# K10P100_V1_0.net
KiCad netlist of a schematic drawn in Altium Designer
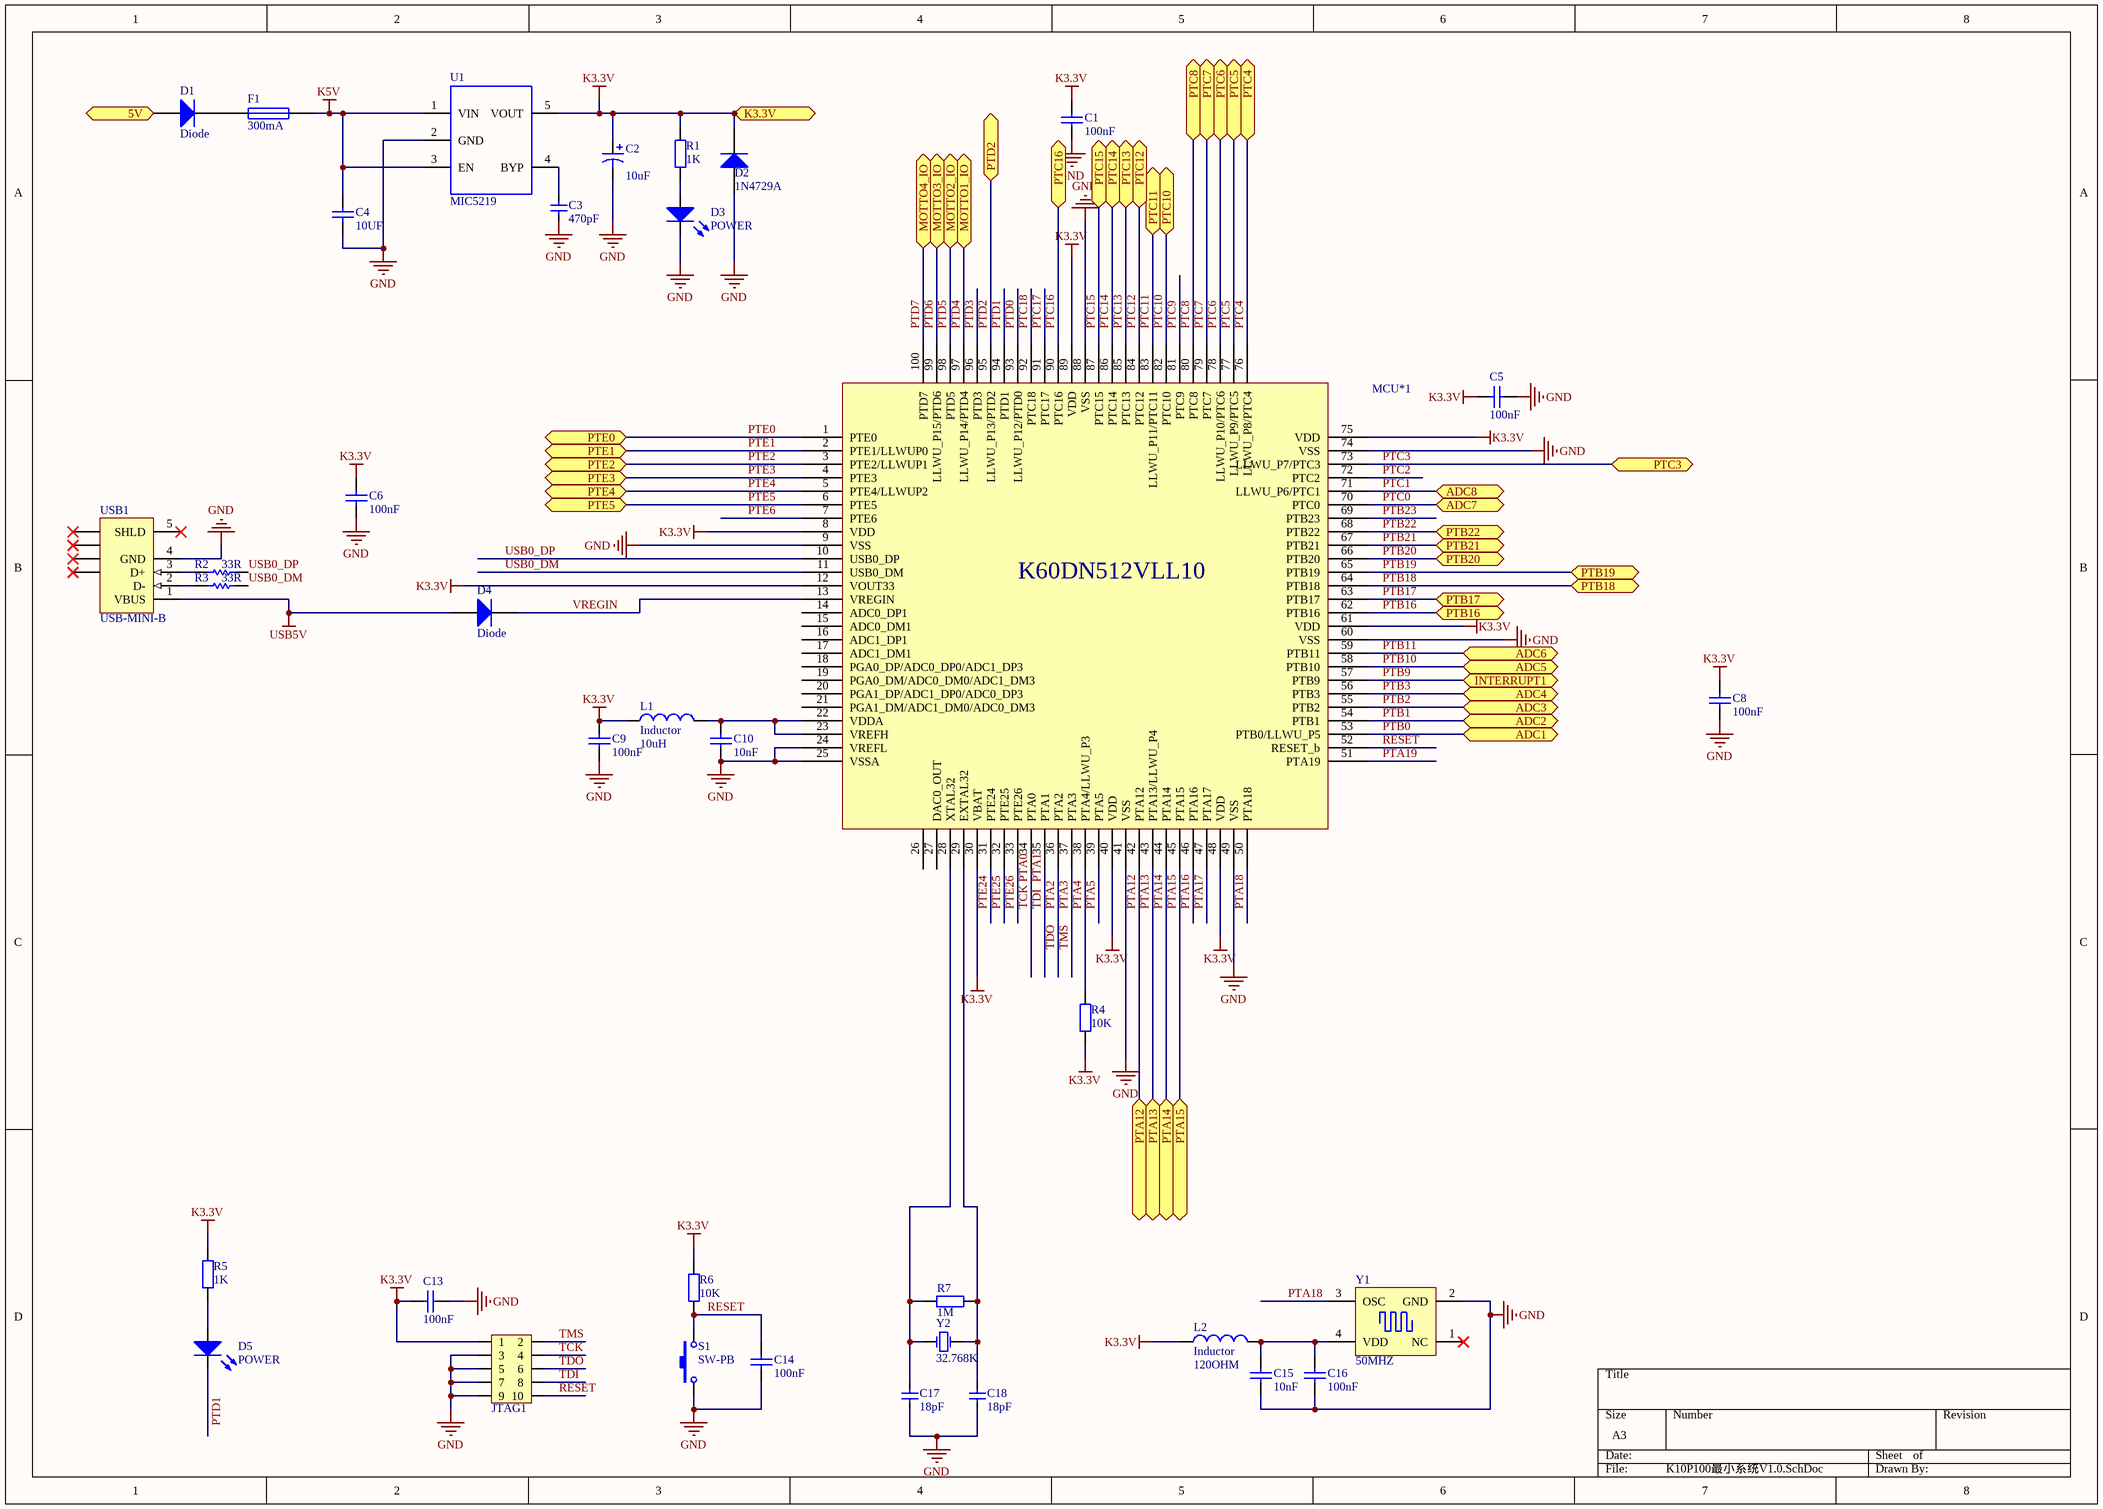
[diagram p0: K10P100最小系统V1.0.SchDoc]

(export (version "E")
  (design (tool "Eeschema 10.0.6"))
  (components
    (comp (ref "C1")
      (value "100nF")
      (footprint "C2012")
      (description "Capacitor")
      (libsource (lib "K60-V4.0") (part "Cap"))
    )
    (comp (ref "C2")
      (value "10uF")
      (footprint "C2012")
      (description "Polarized Capacitor (Radial)")
      (fields (field (name "Comment") "Cap Pol1") (field (name "PUBLISHER") "Altium Limited"))
      (libsource (lib "Miscellaneous Devices") (part "Cap Pol1"))
    )
    (comp (ref "C3")
      (value "470pF")
      (footprint "C2012")
      (description "CAP")
      (libsource (lib "K60-V4.0") (part "陶瓷电容"))
    )
    (comp (ref "C4")
      (value "10UF")
      (footprint "C2012")
      (description "Capacitor")
      (libsource (lib "K60-V4.0") (part "Cap"))
    )
    (comp (ref "C5")
      (value "100nF")
      (footprint "C2012")
      (description "Capacitor")
      (libsource (lib "K60-V4.0") (part "Cap"))
    )
    (comp (ref "C6")
      (value "100nF")
      (footprint "C2012")
      (description "Capacitor")
      (libsource (lib "K60-V4.0") (part "Cap"))
    )
    (comp (ref "C8")
      (value "100nF")
      (footprint "C2012")
      (description "Capacitor")
      (libsource (lib "K60-V4.0") (part "Cap"))
    )
    (comp (ref "C9")
      (value "100nF")
      (footprint "C2012")
      (description "Capacitor")
      (libsource (lib "K60-V4.0") (part "Cap"))
    )
    (comp (ref "C10")
      (value "10nF")
      (footprint "C2012")
      (description "Capacitor")
      (libsource (lib "K60-V4.0") (part "Cap"))
    )
    (comp (ref "C13")
      (value "100nF")
      (footprint "C2012")
      (description "Capacitor")
      (libsource (lib "K60-V4.0") (part "Cap"))
    )
    (comp (ref "C14")
      (value "100nF")
      (footprint "C2012")
      (description "Capacitor")
      (libsource (lib "K60-V4.0") (part "Cap"))
    )
    (comp (ref "C15")
      (value "10nF")
      (footprint "C2012")
      (description "Capacitor")
      (libsource (lib "K60-V4.0") (part "Cap"))
    )
    (comp (ref "C16")
      (value "100nF")
      (footprint "C2012")
      (description "Capacitor")
      (libsource (lib "K60-V4.0") (part "Cap"))
    )
    (comp (ref "C17")
      (value "18pF")
      (footprint "C2012")
      (description "CAP")
      (libsource (lib "K60-V4.0") (part "陶瓷电容"))
    )
    (comp (ref "C18")
      (value "18pF")
      (footprint "C2012")
      (description "CAP")
      (libsource (lib "K60-V4.0") (part "陶瓷电容"))
    )
    (comp (ref "D1")
      (value "Diode")
      (footprint "1206(2)")
      (description "Default Diode")
      (fields (field (name "PUBLISHER") "Altium Limited"))
      (libsource (lib "Miscellaneous Devices") (part "Diode"))
    )
    (comp (ref "D2")
      (value "1N4729A")
      (footprint "C2012")
      (description "High Conductance Fast Diode")
      (fields (field (name "PUBLISHER") "Altium Limited"))
      (libsource (lib "K60-V4.0") (part "Diode 1N4148"))
    )
    (comp (ref "D3")
      (value "POWER")
      (footprint "C2012")
      (description "Typical INFRARED GaAs LED")
      (libsource (lib "K60-V4.0") (part "LED"))
    )
    (comp (ref "D4")
      (value "Diode")
      (footprint "1206(2)")
      (description "Default Diode")
      (fields (field (name "PUBLISHER") "Altium Limited"))
      (libsource (lib "Miscellaneous Devices") (part "Diode"))
    )
    (comp (ref "D5")
      (value "POWER")
      (footprint "C2012")
      (description "Typical INFRARED GaAs LED")
      (libsource (lib "K60-V4.0") (part "LED"))
    )
    (comp (ref "F1")
      (value "300mA")
      (footprint "R2012")
      (description "Fuse")
      (fields (field (name "PUBLISHER") "Altium Limited"))
      (libsource (lib "K60-V4.0") (part "Fuse 1"))
    )
    (comp (ref "JTAG1")
      (value "Header 5X2")
      (footprint "IDC5X2")
      (description "Header, 5-Pin, Dual row")
      (libsource (lib "K60-V4.0") (part "Header 5X2"))
    )
    (comp (ref "L1")
      (value "Inductor")
      (footprint "C2012")
      (fields (field (name "ALTIUM_VALUE") "10uH") (field (name "PUBLISHER") "Altium Limited"))
      (libsource (lib "Miscellaneous Devices") (part "Inductor"))
    )
    (comp (ref "L2")
      (value "Inductor")
      (footprint "C2012")
      (fields (field (name "ALTIUM_VALUE") "120OHM") (field (name "PUBLISHER") "Altium Limited"))
      (libsource (lib "Miscellaneous Devices") (part "Inductor"))
    )
    (comp (ref "MCU*1") (value "k60P100") (footprint "LQFP100") (libsource (lib "原理图") (part "k60P100")))
    (comp (ref "R1")
      (value "1K")
      (footprint "R2012")
      (description "Resistor of led")
      (libsource (lib "K60-V4.0") (part "Res"))
    )
    (comp (ref "R2")
      (value "33R")
      (footprint "R2012")
      (description "贴片电阻")
      (fields (field (name "PUBLISHER") "Altium Limited"))
      (libsource (lib "Sparks") (part "Res"))
    )
    (comp (ref "R3")
      (value "33R")
      (footprint "R2012")
      (description "贴片电阻")
      (fields (field (name "PUBLISHER") "Altium Limited"))
      (libsource (lib "Sparks") (part "Res"))
    )
    (comp (ref "R4")
      (value "10K")
      (footprint "R2012")
      (description "Resistor of led")
      (libsource (lib "K60-V4.0") (part "Res"))
    )
    (comp (ref "R5")
      (value "1K")
      (footprint "R2012")
      (description "Resistor of led")
      (libsource (lib "K60-V4.0") (part "Res"))
    )
    (comp (ref "R6")
      (value "10K")
      (footprint "R2012")
      (description "Resistor")
      (libsource (lib "K60-V4.0") (part "Res"))
    )
    (comp (ref "R7")
      (value "1M")
      (footprint "R2012")
      (description "Resistor")
      (libsource (lib "") (part "Res_1"))
    )
    (comp (ref "S1")
      (value "SW-PB")
      (footprint "sw 3*4 *2")
      (description "Switch")
      (libsource (lib "K60-V4.0") (part "SW-PB"))
    )
    (comp (ref "U1")
      (value "MIC5219")
      (footprint "SOT-23-5")
      (description "LDO")
      (libsource (lib "K60-V4.0") (part "MIC5219"))
    )
    (comp (ref "USB1")
      (value "USB-MINI-B")
      (footprint "USB-MINI-B")
      (description "USB 2.0, Right Angle, SMT, A Type, Receptacle, 5 Position, Black")
      (fields (field (name "PUBLISHER") "Altium Limited"))
      (libsource (lib "Sparks") (part "USB-MINI-B"))
    )
    (comp (ref "Y1") (value "50MHZ") (footprint "XTAL7_3225") (libsource (lib "K60-V4.0") (part "XTAL1")))
    (comp (ref "Y2")
      (value "32.768K")
      (footprint "CT3215")
      (description "Crystal Oscillator")
      (libsource (lib "K60-V4.0") (part "XTAL"))
    )
  )
  (nets
    (net (code "1") (name "/5V") (class "Default")
      (node (ref "D1") (pin "1") (pinfunction "A_1") (pintype "passive"))
    )
    (net (code "2") (name "/PTA0") (class "Default")
      (node (ref "JTAG1") (pin "4") (pinfunction "4_4") (pintype "passive"))
      (node (ref "MCU*1") (pin "34") (pinfunction "PTA0_34") (pintype "passive"))
    )
    (net (code "3") (name "/PTA1") (class "Default")
      (node (ref "JTAG1") (pin "8") (pinfunction "8_8") (pintype "passive"))
      (node (ref "MCU*1") (pin "35") (pinfunction "PTA1_35") (pintype "passive"))
    )
    (net (code "4") (name "/PTA2") (class "Default")
      (node (ref "JTAG1") (pin "6") (pinfunction "6_6") (pintype "passive"))
      (node (ref "MCU*1") (pin "36") (pinfunction "PTA2_36") (pintype "passive"))
    )
    (net (code "5") (name "/PTA3") (class "Default")
      (node (ref "JTAG1") (pin "2") (pinfunction "2_2") (pintype "passive"))
      (node (ref "MCU*1") (pin "37") (pinfunction "PTA3_37") (pintype "passive"))
    )
    (net (code "6") (name "/PTA4") (class "Default")
      (node (ref "MCU*1") (pin "38") (pinfunction "PTA4/LLWU_P3_38") (pintype "passive"))
      (node (ref "R4") (pin "2") (pinfunction "2_2") (pintype "passive"))
    )
    (net (code "7") (name "/PTA5") (class "Default")
      (node (ref "MCU*1") (pin "39") (pinfunction "PTA5_39") (pintype "passive"))
    )
    (net (code "8") (name "/PTA12") (class "Default")
      (node (ref "MCU*1") (pin "42") (pinfunction "PTA12_42") (pintype "passive"))
    )
    (net (code "9") (name "/PTA13") (class "Default")
      (node (ref "MCU*1") (pin "43") (pinfunction "PTA13/LLWU_P4_43") (pintype "passive"))
    )
    (net (code "10") (name "/PTA14") (class "Default")
      (node (ref "MCU*1") (pin "44") (pinfunction "PTA14_44") (pintype "passive"))
    )
    (net (code "11") (name "/PTA15") (class "Default")
      (node (ref "MCU*1") (pin "45") (pinfunction "PTA15_45") (pintype "passive"))
    )
    (net (code "12") (name "/PTA16") (class "Default")
      (node (ref "MCU*1") (pin "46") (pinfunction "PTA16_46") (pintype "passive"))
    )
    (net (code "13") (name "/PTA17") (class "Default")
      (node (ref "MCU*1") (pin "47") (pinfunction "PTA17_47") (pintype "passive"))
    )
    (net (code "14") (name "/PTA18") (class "Default")
      (node (ref "MCU*1") (pin "50") (pinfunction "PTA18_50") (pintype "passive"))
      (node (ref "Y1") (pin "3") (pinfunction "OSC_3") (pintype "passive"))
    )
    (net (code "15") (name "/PTA19") (class "Default")
      (node (ref "MCU*1") (pin "51") (pinfunction "PTA19_51") (pintype "passive"))
    )
    (net (code "16") (name "/PTB0") (class "Default")
      (node (ref "MCU*1") (pin "53") (pinfunction "PTB0/LLWU_P5_53") (pintype "passive"))
    )
    (net (code "17") (name "/PTB1") (class "Default")
      (node (ref "MCU*1") (pin "54") (pinfunction "PTB1_54") (pintype "passive"))
    )
    (net (code "18") (name "/PTB2") (class "Default")
      (node (ref "MCU*1") (pin "55") (pinfunction "PTB2_55") (pintype "passive"))
    )
    (net (code "19") (name "/PTB3") (class "Default")
      (node (ref "MCU*1") (pin "56") (pinfunction "PTB3_56") (pintype "passive"))
    )
    (net (code "20") (name "/PTB9") (class "Default")
      (node (ref "MCU*1") (pin "57") (pinfunction "PTB9_57") (pintype "passive"))
    )
    (net (code "21") (name "/PTB10") (class "Default")
      (node (ref "MCU*1") (pin "58") (pinfunction "PTB10_58") (pintype "passive"))
    )
    (net (code "22") (name "/PTB11") (class "Default")
      (node (ref "MCU*1") (pin "59") (pinfunction "PTB11_59") (pintype "passive"))
    )
    (net (code "23") (name "/PTB16") (class "Default")
      (node (ref "MCU*1") (pin "62") (pinfunction "PTB16_62") (pintype "passive"))
    )
    (net (code "24") (name "/PTB17") (class "Default")
      (node (ref "MCU*1") (pin "63") (pinfunction "PTB17_63") (pintype "passive"))
    )
    (net (code "25") (name "/PTB18") (class "Default")
      (node (ref "MCU*1") (pin "64") (pinfunction "PTB18_64") (pintype "passive"))
    )
    (net (code "26") (name "/PTB19") (class "Default")
      (node (ref "MCU*1") (pin "65") (pinfunction "PTB19_65") (pintype "passive"))
    )
    (net (code "27") (name "/PTB20") (class "Default")
      (node (ref "MCU*1") (pin "66") (pinfunction "PTB20_66") (pintype "passive"))
    )
    (net (code "28") (name "/PTB21") (class "Default")
      (node (ref "MCU*1") (pin "67") (pinfunction "PTB21_67") (pintype "passive"))
    )
    (net (code "29") (name "/PTB22") (class "Default")
      (node (ref "MCU*1") (pin "68") (pinfunction "PTB22_68") (pintype "passive"))
    )
    (net (code "30") (name "/PTB23") (class "Default")
      (node (ref "MCU*1") (pin "69") (pinfunction "PTB23_69") (pintype "passive"))
    )
    (net (code "31") (name "/PTC0") (class "Default")
      (node (ref "MCU*1") (pin "70") (pinfunction "PTC0_70") (pintype "passive"))
    )
    (net (code "32") (name "/PTC1") (class "Default")
      (node (ref "MCU*1") (pin "71") (pinfunction "LLWU_P6/PTC1_71") (pintype "passive"))
    )
    (net (code "33") (name "/PTC2") (class "Default")
      (node (ref "MCU*1") (pin "72") (pinfunction "PTC2_72") (pintype "passive"))
    )
    (net (code "34") (name "/PTC3") (class "Default")
      (node (ref "MCU*1") (pin "73") (pinfunction "LLWU_P7/PTC3_73") (pintype "passive"))
    )
    (net (code "35") (name "/PTC4") (class "Default")
      (node (ref "MCU*1") (pin "76") (pinfunction "LLWU_P8/PTC4_76") (pintype "passive"))
    )
    (net (code "36") (name "/PTC5") (class "Default")
      (node (ref "MCU*1") (pin "77") (pinfunction "LLWU_P9/PTC5_77") (pintype "passive"))
    )
    (net (code "37") (name "/PTC6") (class "Default")
      (node (ref "MCU*1") (pin "78") (pinfunction "LLWU_P10/PTC6_78") (pintype "passive"))
    )
    (net (code "38") (name "/PTC7") (class "Default")
      (node (ref "MCU*1") (pin "79") (pinfunction "PTC7_79") (pintype "passive"))
    )
    (net (code "39") (name "/PTC8") (class "Default")
      (node (ref "MCU*1") (pin "80") (pinfunction "PTC8_80") (pintype "passive"))
    )
    (net (code "40") (name "/PTC9") (class "Default")
      (node (ref "MCU*1") (pin "81") (pinfunction "PTC9_81") (pintype "passive"))
    )
    (net (code "41") (name "/PTC10") (class "Default")
      (node (ref "MCU*1") (pin "82") (pinfunction "PTC10_82") (pintype "passive"))
    )
    (net (code "42") (name "/PTC11") (class "Default")
      (node (ref "MCU*1") (pin "83") (pinfunction "LLWU_P11/PTC11_83") (pintype "passive"))
    )
    (net (code "43") (name "/PTC12") (class "Default")
      (node (ref "MCU*1") (pin "84") (pinfunction "PTC12_84") (pintype "passive"))
    )
    (net (code "44") (name "/PTC13") (class "Default")
      (node (ref "MCU*1") (pin "85") (pinfunction "PTC13_85") (pintype "passive"))
    )
    (net (code "45") (name "/PTC14") (class "Default")
      (node (ref "MCU*1") (pin "86") (pinfunction "PTC14_86") (pintype "passive"))
    )
    (net (code "46") (name "/PTC15") (class "Default")
      (node (ref "MCU*1") (pin "87") (pinfunction "PTC15_87") (pintype "passive"))
    )
    (net (code "47") (name "/PTC16") (class "Default")
      (node (ref "MCU*1") (pin "90") (pinfunction "PTC16_90") (pintype "passive"))
    )
    (net (code "48") (name "/PTC17") (class "Default")
      (node (ref "MCU*1") (pin "91") (pinfunction "PTC17_91") (pintype "passive"))
    )
    (net (code "49") (name "/PTC18") (class "Default")
      (node (ref "MCU*1") (pin "92") (pinfunction "PTC18_92") (pintype "passive"))
    )
    (net (code "50") (name "/PTD0") (class "Default")
      (node (ref "MCU*1") (pin "93") (pinfunction "LLWU_P12/PTD0_93") (pintype "passive"))
    )
    (net (code "51") (name "/PTD1") (class "Default")
      (node (ref "D5") (pin "2") (pinfunction "2_2") (pintype "passive"))
      (node (ref "MCU*1") (pin "94") (pinfunction "PTD1_94") (pintype "passive"))
    )
    (net (code "52") (name "/PTD2") (class "Default")
      (node (ref "MCU*1") (pin "95") (pinfunction "LLWU_P13/PTD2_95") (pintype "passive"))
    )
    (net (code "53") (name "/PTD3") (class "Default")
      (node (ref "MCU*1") (pin "96") (pinfunction "PTD3_96") (pintype "passive"))
    )
    (net (code "54") (name "/PTD4") (class "Default")
      (node (ref "MCU*1") (pin "97") (pinfunction "LLWU_P14/PTD4_97") (pintype "passive"))
    )
    (net (code "55") (name "/PTD5") (class "Default")
      (node (ref "MCU*1") (pin "98") (pinfunction "PTD5_98") (pintype "passive"))
    )
    (net (code "56") (name "/PTD6") (class "Default")
      (node (ref "MCU*1") (pin "99") (pinfunction "LLWU_P15/PTD6_99") (pintype "passive"))
    )
    (net (code "57") (name "/PTD7") (class "Default")
      (node (ref "MCU*1") (pin "100") (pinfunction "PTD7_100") (pintype "passive"))
    )
    (net (code "58") (name "/PTE0") (class "Default")
      (node (ref "MCU*1") (pin "1") (pinfunction "PTE0_1") (pintype "passive"))
    )
    (net (code "59") (name "/PTE1") (class "Default")
      (node (ref "MCU*1") (pin "2") (pinfunction "PTE1/LLWUP0_2") (pintype "passive"))
    )
    (net (code "60") (name "/PTE2") (class "Default")
      (node (ref "MCU*1") (pin "3") (pinfunction "PTE2/LLWUP1_3") (pintype "passive"))
    )
    (net (code "61") (name "/PTE3") (class "Default")
      (node (ref "MCU*1") (pin "4") (pinfunction "PTE3_4") (pintype "passive"))
    )
    (net (code "62") (name "/PTE4") (class "Default")
      (node (ref "MCU*1") (pin "5") (pinfunction "PTE4/LLWUP2_5") (pintype "passive"))
    )
    (net (code "63") (name "/PTE5") (class "Default")
      (node (ref "MCU*1") (pin "6") (pinfunction "PTE5_6") (pintype "passive"))
    )
    (net (code "64") (name "/PTE6") (class "Default")
      (node (ref "MCU*1") (pin "7") (pinfunction "PTE6_7") (pintype "passive"))
    )
    (net (code "65") (name "/PTE24") (class "Default")
      (node (ref "MCU*1") (pin "31") (pinfunction "PTE24_31") (pintype "passive"))
    )
    (net (code "66") (name "/PTE25") (class "Default")
      (node (ref "MCU*1") (pin "32") (pinfunction "PTE25_32") (pintype "passive"))
    )
    (net (code "67") (name "/PTE26") (class "Default")
      (node (ref "MCU*1") (pin "33") (pinfunction "PTE26_33") (pintype "passive"))
    )
    (net (code "68") (name "/RESET") (class "Default")
      (node (ref "C14") (pin "2") (pinfunction "2_2") (pintype "passive"))
      (node (ref "JTAG1") (pin "10") (pinfunction "10_10") (pintype "passive"))
      (node (ref "MCU*1") (pin "52") (pinfunction "RESET_b_52") (pintype "passive"))
      (node (ref "R6") (pin "1") (pinfunction "1_1") (pintype "passive"))
      (node (ref "S1") (pin "2") (pinfunction "2_2") (pintype "passive"))
    )
    (net (code "69") (name "/USB0_DM") (class "Default")
      (node (ref "MCU*1") (pin "11") (pinfunction "USB0_DM_11") (pintype "passive"))
      (node (ref "R3") (pin "2") (pinfunction "2_2") (pintype "passive"))
    )
    (net (code "70") (name "/USB0_DP") (class "Default")
      (node (ref "MCU*1") (pin "10") (pinfunction "USB0_DP_10") (pintype "passive"))
      (node (ref "R2") (pin "2") (pinfunction "2_2") (pintype "passive"))
    )
    (net (code "71") (name "/VREGIN") (class "Default")
      (node (ref "D4") (pin "2") (pinfunction "K_2") (pintype "passive"))
      (node (ref "MCU*1") (pin "13") (pinfunction "VREGIN_13") (pintype "passive"))
    )
    (net (code "72") (name "GND") (class "Default")
      (node (ref "C1") (pin "1") (pinfunction "1_1") (pintype "passive"))
      (node (ref "C10") (pin "1") (pinfunction "1_1") (pintype "passive"))
      (node (ref "C13") (pin "2") (pinfunction "2_2") (pintype "passive"))
      (node (ref "C14") (pin "1") (pinfunction "1_1") (pintype "passive"))
      (node (ref "C15") (pin "1") (pinfunction "1_1") (pintype "passive"))
      (node (ref "C16") (pin "1") (pinfunction "1_1") (pintype "passive"))
      (node (ref "C17") (pin "1") (pinfunction "1_1") (pintype "passive"))
      (node (ref "C18") (pin "1") (pinfunction "1_1") (pintype "passive"))
      (node (ref "C2") (pin "2") (pinfunction "2_2") (pintype "passive"))
      (node (ref "C3") (pin "1") (pinfunction "1_1") (pintype "passive"))
      (node (ref "C4") (pin "1") (pinfunction "1_1") (pintype "passive"))
      (node (ref "C5") (pin "1") (pinfunction "1_1") (pintype "passive"))
      (node (ref "C6") (pin "1") (pinfunction "1_1") (pintype "passive"))
      (node (ref "C8") (pin "1") (pinfunction "1_1") (pintype "passive"))
      (node (ref "C9") (pin "1") (pinfunction "1_1") (pintype "passive"))
      (node (ref "D2") (pin "1") (pinfunction "A_1") (pintype "passive"))
      (node (ref "D3") (pin "2") (pinfunction "2_2") (pintype "passive"))
      (node (ref "JTAG1") (pin "3") (pinfunction "3_3") (pintype "passive"))
      (node (ref "JTAG1") (pin "5") (pinfunction "5_5") (pintype "passive"))
      (node (ref "JTAG1") (pin "7") (pinfunction "7_7") (pintype "passive"))
      (node (ref "JTAG1") (pin "9") (pinfunction "9_9") (pintype "passive"))
      (node (ref "MCU*1") (pin "24") (pinfunction "VREFL_24") (pintype "passive"))
      (node (ref "MCU*1") (pin "25") (pinfunction "VSSA_25") (pintype "passive"))
      (node (ref "MCU*1") (pin "41") (pinfunction "VSS_41") (pintype "passive"))
      (node (ref "MCU*1") (pin "49") (pinfunction "VSS_49") (pintype "passive"))
      (node (ref "MCU*1") (pin "60") (pinfunction "VSS_60") (pintype "passive"))
      (node (ref "MCU*1") (pin "74") (pinfunction "VSS_74") (pintype "passive"))
      (node (ref "MCU*1") (pin "88") (pinfunction "VSS_88") (pintype "passive"))
      (node (ref "MCU*1") (pin "9") (pinfunction "VSS_9") (pintype "passive"))
      (node (ref "S1") (pin "1") (pinfunction "1_1") (pintype "passive"))
      (node (ref "U1") (pin "2") (pinfunction "GND_2") (pintype "passive"))
      (node (ref "USB1") (pin "4") (pinfunction "GND_4") (pintype "power_in"))
      (node (ref "Y1") (pin "2") (pinfunction "GND_2") (pintype "passive"))
    )
    (net (code "73") (name "K3.3V") (class "Default")
      (node (ref "C1") (pin "2") (pinfunction "2_2") (pintype "passive"))
      (node (ref "C13") (pin "1") (pinfunction "1_1") (pintype "passive"))
      (node (ref "C2") (pin "1") (pinfunction "1_1") (pintype "passive"))
      (node (ref "C5") (pin "2") (pinfunction "2_2") (pintype "passive"))
      (node (ref "C6") (pin "2") (pinfunction "2_2") (pintype "passive"))
      (node (ref "C8") (pin "2") (pinfunction "2_2") (pintype "passive"))
      (node (ref "C9") (pin "2") (pinfunction "2_2") (pintype "passive"))
      (node (ref "D2") (pin "2") (pinfunction "K_2") (pintype "passive"))
      (node (ref "JTAG1") (pin "1") (pinfunction "1_1") (pintype "passive"))
      (node (ref "L1") (pin "1") (pinfunction "1_1") (pintype "passive"))
      (node (ref "L2") (pin "1") (pinfunction "1_1") (pintype "passive"))
      (node (ref "MCU*1") (pin "12") (pinfunction "VOUT33_12") (pintype "passive"))
      (node (ref "MCU*1") (pin "30") (pinfunction "VBAT_30") (pintype "passive"))
      (node (ref "MCU*1") (pin "40") (pinfunction "VDD_40") (pintype "passive"))
      (node (ref "MCU*1") (pin "48") (pinfunction "VDD_48") (pintype "passive"))
      (node (ref "MCU*1") (pin "61") (pinfunction "VDD_61") (pintype "passive"))
      (node (ref "MCU*1") (pin "75") (pinfunction "VDD_75") (pintype "passive"))
      (node (ref "MCU*1") (pin "8") (pinfunction "VDD_8") (pintype "passive"))
      (node (ref "MCU*1") (pin "89") (pinfunction "VDD_89") (pintype "passive"))
      (node (ref "R1") (pin "2") (pinfunction "2_2") (pintype "passive"))
      (node (ref "R4") (pin "1") (pinfunction "1_1") (pintype "passive"))
      (node (ref "R5") (pin "2") (pinfunction "2_2") (pintype "passive"))
      (node (ref "R6") (pin "2") (pinfunction "2_2") (pintype "passive"))
      (node (ref "U1") (pin "5") (pinfunction "VOUT_5") (pintype "passive"))
    )
    (net (code "74") (name "K5V") (class "Default")
      (node (ref "C4") (pin "2") (pinfunction "2_2") (pintype "passive"))
      (node (ref "F1") (pin "1") (pinfunction "1_1") (pintype "passive"))
      (node (ref "U1") (pin "1") (pinfunction "VIN_1") (pintype "passive"))
      (node (ref "U1") (pin "3") (pinfunction "EN_3") (pintype "passive"))
    )
    (net (code "75") (name "Net-(D1-K)") (class "Default")
      (node (ref "D1") (pin "2") (pinfunction "K_2") (pintype "passive"))
      (node (ref "F1") (pin "2") (pinfunction "2_2") (pintype "passive"))
    )
    (net (code "76") (name "Net-(D3-Pad1)") (class "Default")
      (node (ref "D3") (pin "1") (pinfunction "1_1") (pintype "passive"))
      (node (ref "R1") (pin "1") (pinfunction "1_1") (pintype "passive"))
    )
    (net (code "77") (name "Net-(D5-Pad1)") (class "Default")
      (node (ref "D5") (pin "1") (pinfunction "1_1") (pintype "passive"))
      (node (ref "R5") (pin "1") (pinfunction "1_1") (pintype "passive"))
    )
    (net (code "78") (name "Net-(MCU*1-EXTAL32)") (class "Default")
      (node (ref "C18") (pin "2") (pinfunction "2_2") (pintype "passive"))
      (node (ref "MCU*1") (pin "29") (pinfunction "EXTAL32_29") (pintype "passive"))
      (node (ref "R7") (pin "2") (pinfunction "2_2") (pintype "passive"))
      (node (ref "Y2") (pin "2") (pinfunction "OSC2_2") (pintype "passive"))
    )
    (net (code "79") (name "Net-(MCU*1-VDDA)") (class "Default")
      (node (ref "C10") (pin "2") (pinfunction "2_2") (pintype "passive"))
      (node (ref "L1") (pin "2") (pinfunction "2_2") (pintype "passive"))
      (node (ref "MCU*1") (pin "22") (pinfunction "VDDA_22") (pintype "passive"))
      (node (ref "MCU*1") (pin "23") (pinfunction "VREFH_23") (pintype "passive"))
    )
    (net (code "80") (name "Net-(MCU*1-XTAL32)") (class "Default")
      (node (ref "C17") (pin "2") (pinfunction "2_2") (pintype "passive"))
      (node (ref "MCU*1") (pin "28") (pinfunction "XTAL32_28") (pintype "passive"))
      (node (ref "R7") (pin "1") (pinfunction "1_1") (pintype "passive"))
      (node (ref "Y2") (pin "1") (pinfunction "OSC1_1") (pintype "passive"))
    )
    (net (code "81") (name "Net-(U1-BYP)") (class "Default")
      (node (ref "C3") (pin "2") (pinfunction "2_2") (pintype "passive"))
      (node (ref "U1") (pin "4") (pinfunction "BYP_4") (pintype "passive"))
    )
    (net (code "82") (name "Net-(USB1-D+)") (class "Default")
      (node (ref "R2") (pin "1") (pinfunction "1_1") (pintype "passive"))
      (node (ref "USB1") (pin "3") (pinfunction "D+_3") (pintype "input"))
    )
    (net (code "83") (name "Net-(USB1-D-)") (class "Default")
      (node (ref "R3") (pin "1") (pinfunction "1_1") (pintype "passive"))
      (node (ref "USB1") (pin "2") (pinfunction "D-_2") (pintype "input"))
    )
    (net (code "84") (name "Net-(Y1-VDD)") (class "Default")
      (node (ref "C15") (pin "2") (pinfunction "2_2") (pintype "passive"))
      (node (ref "C16") (pin "2") (pinfunction "2_2") (pintype "passive"))
      (node (ref "L2") (pin "2") (pinfunction "2_2") (pintype "passive"))
      (node (ref "Y1") (pin "4") (pinfunction "VDD_4") (pintype "passive"))
    )
    (net (code "85") (name "USB5V") (class "Default")
      (node (ref "D4") (pin "1") (pinfunction "A_1") (pintype "passive"))
      (node (ref "USB1") (pin "1") (pinfunction "VBUS_1") (pintype "power_in"))
    )
    (net (code "86") (name "unconnected-(MCU*1-ADC0_DM1-Pad15)") (class "Default")
      (node (ref "MCU*1") (pin "15") (pinfunction "ADC0_DM1_15") (pintype "passive"))
    )
    (net (code "87") (name "unconnected-(MCU*1-ADC0_DP1-Pad14)") (class "Default")
      (node (ref "MCU*1") (pin "14") (pinfunction "ADC0_DP1_14") (pintype "passive"))
    )
    (net (code "88") (name "unconnected-(MCU*1-ADC1_DM1-Pad17)") (class "Default")
      (node (ref "MCU*1") (pin "17") (pinfunction "ADC1_DM1_17") (pintype "passive"))
    )
    (net (code "89") (name "unconnected-(MCU*1-ADC1_DP1-Pad16)") (class "Default")
      (node (ref "MCU*1") (pin "16") (pinfunction "ADC1_DP1_16") (pintype "passive"))
    )
    (net (code "90") (name "unconnected-(MCU*1-DAC0_OUT-Pad27)") (class "Default")
      (node (ref "MCU*1") (pin "27") (pinfunction "DAC0_OUT_27") (pintype "passive"))
    )
    (net (code "91") (name "unconnected-(MCU*1-PGA0_DM{slash}ADC0_DM0{slash}ADC1_DM3-Pad19)") (class "Default")
      (node (ref "MCU*1") (pin "19") (pinfunction "PGA0_DM/ADC0_DM0/ADC1_DM3_19") (pintype "passive"))
    )
    (net (code "92") (name "unconnected-(MCU*1-PGA0_DP{slash}ADC0_DP0{slash}ADC1_DP3-Pad18)") (class "Default")
      (node (ref "MCU*1") (pin "18") (pinfunction "PGA0_DP/ADC0_DP0/ADC1_DP3_18") (pintype "passive"))
    )
    (net (code "93") (name "unconnected-(MCU*1-PGA1_DM{slash}ADC1_DM0{slash}ADC0_DM3-Pad21)") (class "Default")
      (node (ref "MCU*1") (pin "21") (pinfunction "PGA1_DM/ADC1_DM0/ADC0_DM3_21") (pintype "passive"))
    )
    (net (code "94") (name "unconnected-(MCU*1-PGA1_DP{slash}ADC1_DP0{slash}ADC0_DP3-Pad20)") (class "Default")
      (node (ref "MCU*1") (pin "20") (pinfunction "PGA1_DP/ADC1_DP0/ADC0_DP3_20") (pintype "passive"))
    )
    (net (code "95") (name "unconnected-(MCU*1-VREF_OUT{slash}CMP1_IN5CMP0_IN5{slash}ADC1_SE18-Pad26)") (class "Default")
      (node (ref "MCU*1") (pin "26") (pinfunction "VREF_OUT/CMP1_IN5CMP0_IN5/ADC1_SE18_26") (pintype "passive"))
    )
    (net (code "96") (name "unconnected-(USB1-SHLD-Pad5)") (class "Default")
      (node (ref "USB1") (pin "5") (pinfunction "SHLD_5") (pintype "passive+no_connect"))
    )
    (net (code "97") (name "unconnected-(USB1-SHLD-Pad6)") (class "Default")
      (node (ref "USB1") (pin "6") (pinfunction "SHLD_6") (pintype "passive+no_connect"))
    )
    (net (code "98") (name "unconnected-(USB1-SHLD-Pad7)") (class "Default")
      (node (ref "USB1") (pin "7") (pinfunction "SHLD_7") (pintype "passive+no_connect"))
    )
    (net (code "99") (name "unconnected-(USB1-SHLD-Pad8)") (class "Default")
      (node (ref "USB1") (pin "8") (pinfunction "SHLD_8") (pintype "passive+no_connect"))
    )
    (net (code "100") (name "unconnected-(USB1-SHLD-Pad9)") (class "Default")
      (node (ref "USB1") (pin "9") (pinfunction "SHLD_9") (pintype "passive+no_connect"))
    )
    (net (code "101") (name "unconnected-(Y1-NC-Pad1)") (class "Default")
      (node (ref "Y1") (pin "1") (pinfunction "NC_1") (pintype "passive+no_connect"))
    )
  )
)
